# 01_FPGA.net
KiCad netlist of a schematic drawn in Altium Designer
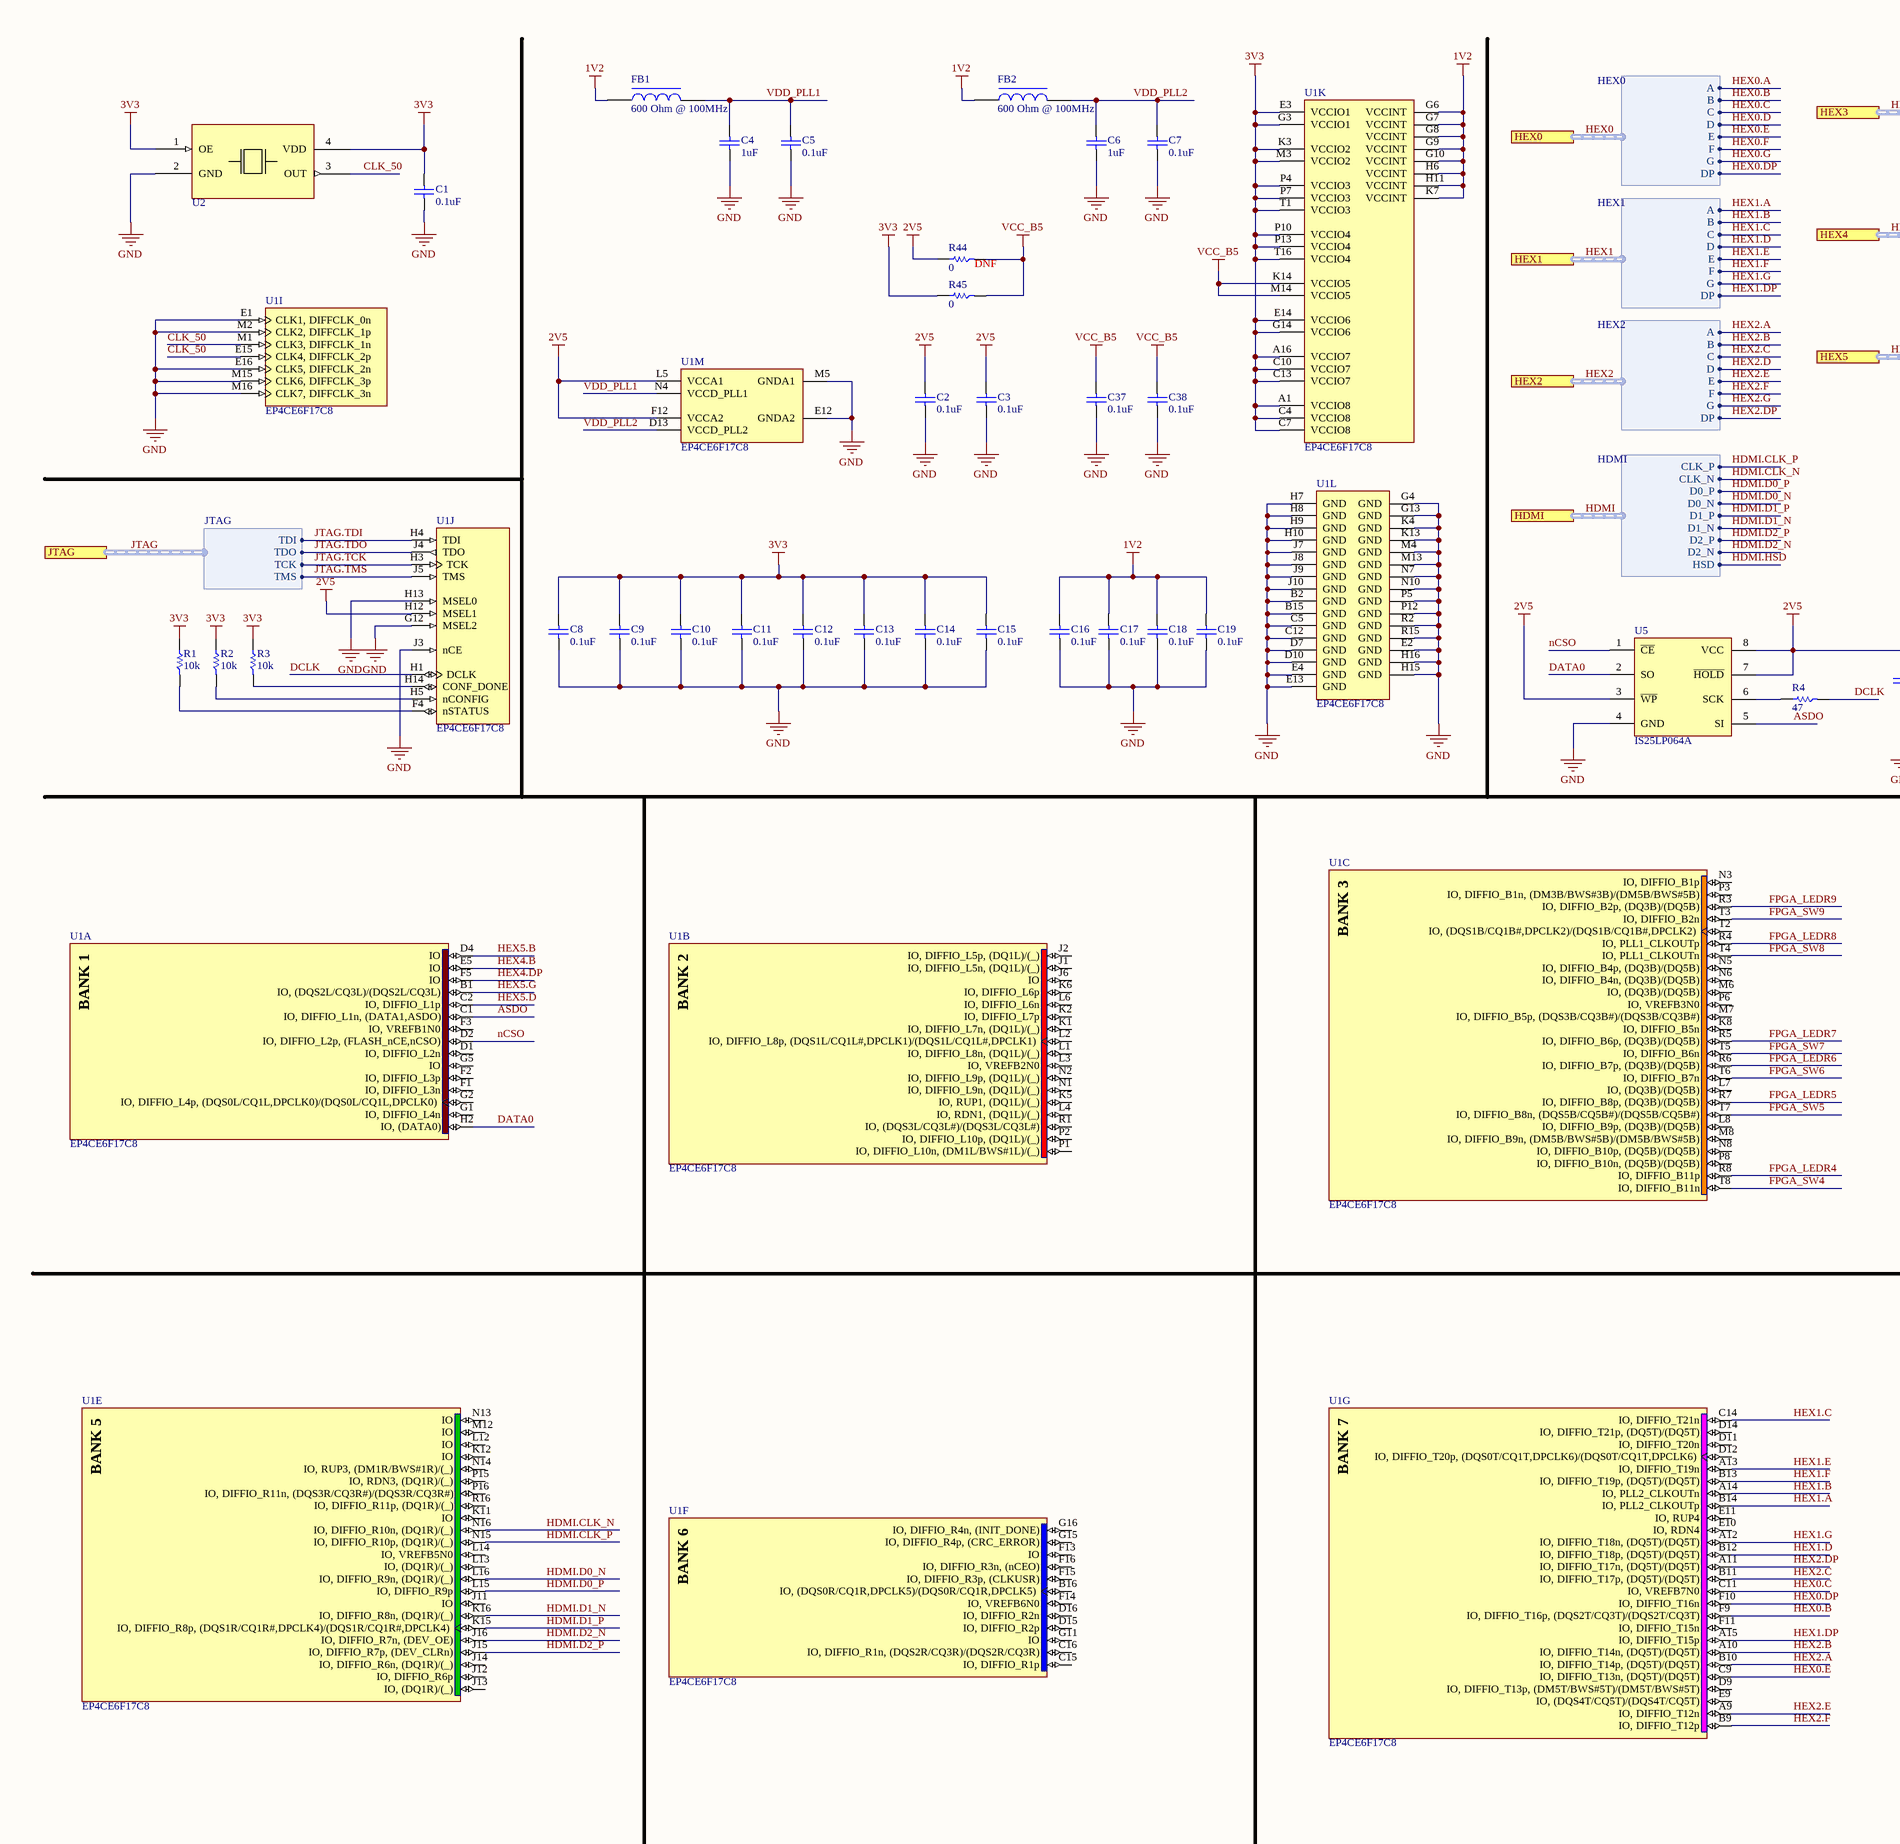
[diagram p0: 01_FPGA.SchDoc, left]
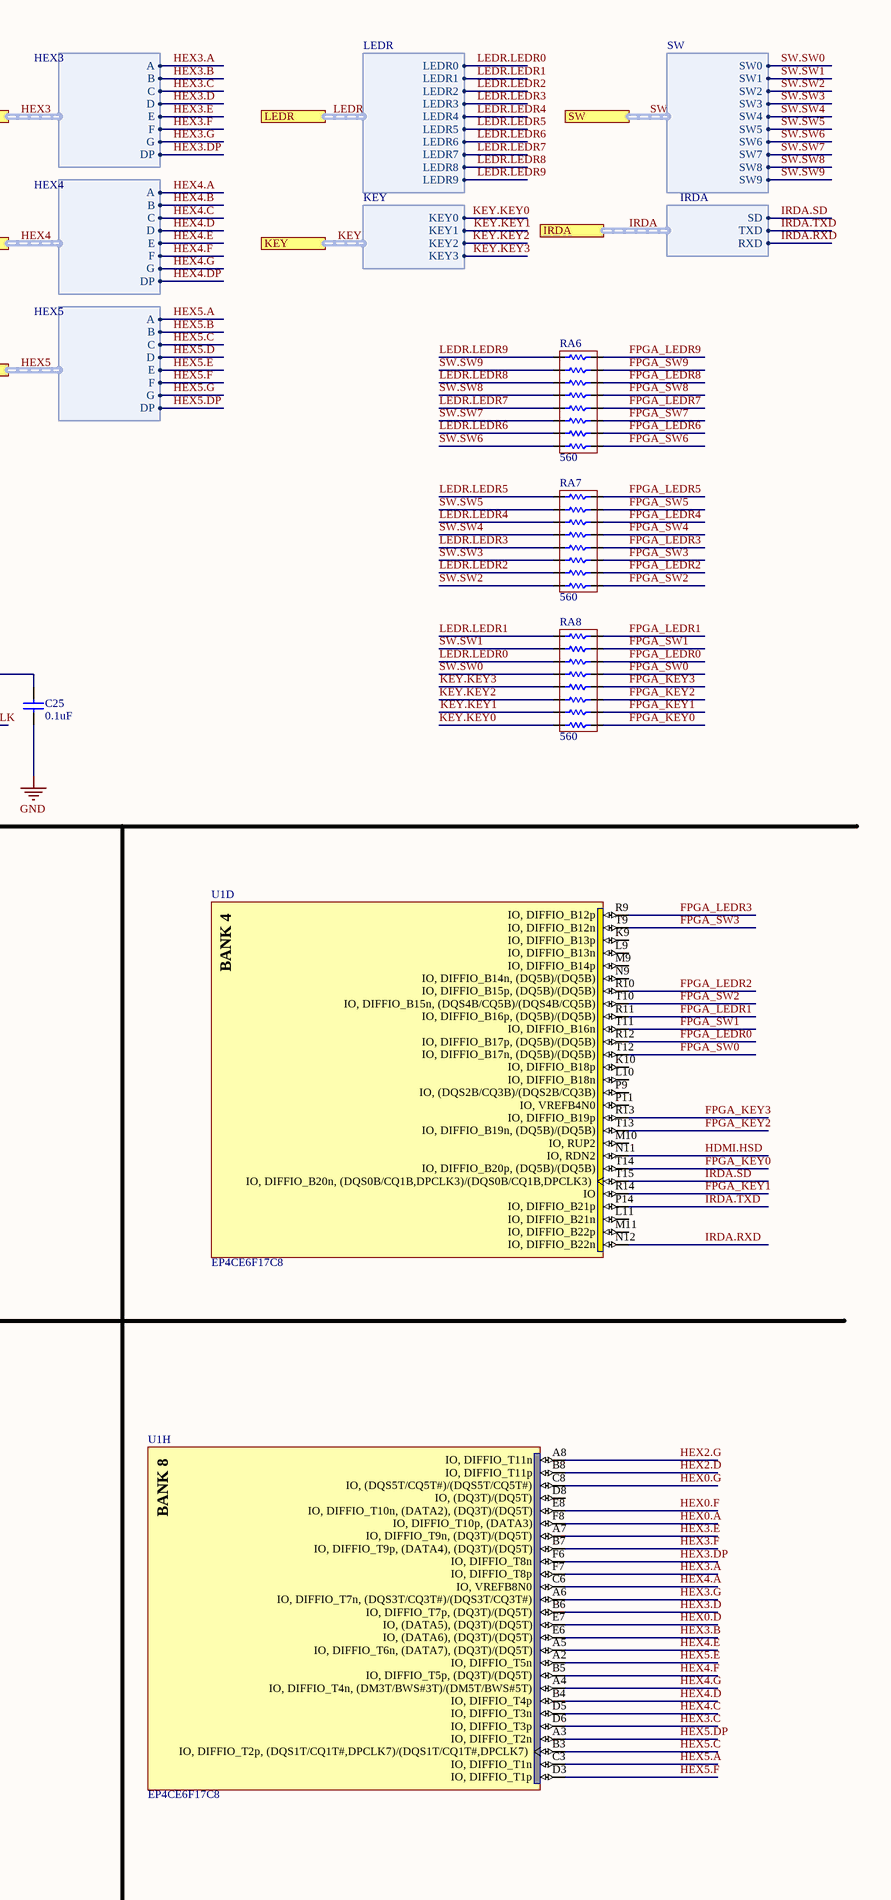
[diagram p1: 01_FPGA.SchDoc, right]

(export (version "E")
  (design (tool "Eeschema 10.0.6"))
  (components
    (comp (ref "C1")
      (value "0.1uF")
      (footprint "CAP0603R")
      (description "Capacitor")
      (libsource (lib "Quatro_SchLib") (part "C"))
    )
    (comp (ref "C2")
      (value "0.1uF")
      (footprint "CAP0603R")
      (description "Capacitor")
      (libsource (lib "Quatro_SchLib") (part "C"))
    )
    (comp (ref "C3")
      (value "0.1uF")
      (footprint "CAP0603R")
      (description "Capacitor")
      (libsource (lib "Quatro_SchLib") (part "C"))
    )
    (comp (ref "C4")
      (value "1uF")
      (footprint "CAP0603R")
      (description "Capacitor")
      (libsource (lib "Quatro_SchLib") (part "C"))
    )
    (comp (ref "C5")
      (value "0.1uF")
      (footprint "CAP0603R")
      (description "Capacitor")
      (libsource (lib "Quatro_SchLib") (part "C"))
    )
    (comp (ref "C6")
      (value "1uF")
      (footprint "CAP0603R")
      (description "Capacitor")
      (libsource (lib "Quatro_SchLib") (part "C"))
    )
    (comp (ref "C7")
      (value "0.1uF")
      (footprint "CAP0603R")
      (description "Capacitor")
      (libsource (lib "Quatro_SchLib") (part "C"))
    )
    (comp (ref "C8")
      (value "0.1uF")
      (footprint "CAP0603R")
      (description "Capacitor")
      (libsource (lib "Quatro_SchLib") (part "C"))
    )
    (comp (ref "C9")
      (value "0.1uF")
      (footprint "CAP0603R")
      (description "Capacitor")
      (libsource (lib "Quatro_SchLib") (part "C"))
    )
    (comp (ref "C10")
      (value "0.1uF")
      (footprint "CAP0603R")
      (description "Capacitor")
      (libsource (lib "Quatro_SchLib") (part "C"))
    )
    (comp (ref "C11")
      (value "0.1uF")
      (footprint "CAP0603R")
      (description "Capacitor")
      (libsource (lib "Quatro_SchLib") (part "C"))
    )
    (comp (ref "C12")
      (value "0.1uF")
      (footprint "CAP0603R")
      (description "Capacitor")
      (libsource (lib "Quatro_SchLib") (part "C"))
    )
    (comp (ref "C13")
      (value "0.1uF")
      (footprint "CAP0603R")
      (description "Capacitor")
      (libsource (lib "Quatro_SchLib") (part "C"))
    )
    (comp (ref "C14")
      (value "0.1uF")
      (footprint "CAP0603R")
      (description "Capacitor")
      (libsource (lib "Quatro_SchLib") (part "C"))
    )
    (comp (ref "C15")
      (value "0.1uF")
      (footprint "CAP0603R")
      (description "Capacitor")
      (libsource (lib "Quatro_SchLib") (part "C"))
    )
    (comp (ref "C16")
      (value "0.1uF")
      (footprint "CAP0603R")
      (description "Capacitor")
      (libsource (lib "Quatro_SchLib") (part "C"))
    )
    (comp (ref "C17")
      (value "0.1uF")
      (footprint "CAP0603R")
      (description "Capacitor")
      (libsource (lib "Quatro_SchLib") (part "C"))
    )
    (comp (ref "C18")
      (value "0.1uF")
      (footprint "CAP0603R")
      (description "Capacitor")
      (libsource (lib "Quatro_SchLib") (part "C"))
    )
    (comp (ref "C19")
      (value "0.1uF")
      (footprint "CAP0603R")
      (description "Capacitor")
      (libsource (lib "Quatro_SchLib") (part "C"))
    )
    (comp (ref "C25")
      (value "0.1uF")
      (footprint "CAP0603R")
      (description "Capacitor")
      (libsource (lib "Quatro_SchLib") (part "C"))
    )
    (comp (ref "C37")
      (value "0.1uF")
      (footprint "CAP0603R")
      (description "Capacitor")
      (libsource (lib "Quatro_SchLib") (part "C"))
    )
    (comp (ref "C38")
      (value "0.1uF")
      (footprint "CAP0603R")
      (description "Capacitor")
      (libsource (lib "Quatro_SchLib") (part "C"))
    )
    (comp (ref "FB1")
      (value "600 Ohm @ 100MHz")
      (footprint "RES0805R")
      (description "Ferrite Bead")
      (libsource (lib "Quatro_SchLib") (part "Ferrite_Bead"))
    )
    (comp (ref "FB2")
      (value "600 Ohm @ 100MHz")
      (footprint "RES0805R")
      (description "Ferrite Bead")
      (libsource (lib "Quatro_SchLib") (part "Ferrite_Bead"))
    )
    (comp (ref "R1")
      (value "10k")
      (footprint "RES0603R")
      (description "Resistor")
      (libsource (lib "Quatro_SchLib") (part "R"))
    )
    (comp (ref "R2")
      (value "10k")
      (footprint "RES0603R")
      (description "Resistor")
      (libsource (lib "Quatro_SchLib") (part "R"))
    )
    (comp (ref "R3")
      (value "10k")
      (footprint "RES0603R")
      (description "Resistor")
      (libsource (lib "Quatro_SchLib") (part "R"))
    )
    (comp (ref "R4")
      (value "47")
      (footprint "RES0603R")
      (description "Resistor")
      (libsource (lib "Quatro_SchLib") (part "R"))
    )
    (comp (ref "R44")
      (value "0")
      (footprint "RES0402R")
      (description "Resistor")
      (fields (field (name "LOAD") "DNF"))
      (libsource (lib "Quatro_SchLib") (part "R"))
    )
    (comp (ref "R45")
      (value "0")
      (footprint "RES0402R")
      (description "Resistor")
      (libsource (lib "Quatro_SchLib") (part "R"))
    )
    (comp (ref "RA6")
      (value "560")
      (footprint "EXB-2HV")
      (description "Resistor Array with 8 Isolated Resistors")
      (fields
        (field (name "Comment") "Resistor Array")
        (field (name "01 CREATED BY") "Thomas Harper (12/03/2017)")
        (field (name "PUBLISHER") "MUEEC")
      )
      (libsource (lib "Quatro_SchLib") (part "Res Array"))
    )
    (comp (ref "RA7")
      (value "560")
      (footprint "EXB-2HV")
      (description "Resistor Array with 8 Isolated Resistors")
      (fields
        (field (name "Comment") "Resistor Array")
        (field (name "01 CREATED BY") "Thomas Harper (12/03/2017)")
        (field (name "PUBLISHER") "MUEEC")
      )
      (libsource (lib "Quatro_SchLib") (part "Res Array"))
    )
    (comp (ref "RA8")
      (value "560")
      (footprint "EXB-2HV")
      (description "Resistor Array with 8 Isolated Resistors")
      (fields
        (field (name "Comment") "Resistor Array")
        (field (name "01 CREATED BY") "Thomas Harper (12/03/2017)")
        (field (name "PUBLISHER") "MUEEC")
      )
      (libsource (lib "Quatro_SchLib") (part "Res Array"))
    )
    (comp (ref "U1")
      (value "EP4CE6F17C8")
      (footprint "FBGA256")
      (fields (field (name "PUBLISHER") "Altium Limited"))
      (libsource (lib "Quatro_SchLib") (part "EP4CE6F17C8"))
    )
    (comp (ref "U2")
      (value "Oscillator")
      (footprint "CRYSTAL_7x5")
      (description "OSC 50MHZ 3.3V SMD")
      (libsource (lib "Quatro_SchLib") (part "CLK_50M"))
    )
    (comp (ref "U5")
      (value "IS25LP064A")
      (footprint "SOIC-8")
      (description "64Mb Serial Flash Memory")
      (libsource (lib "Quatro_SchLib") (part "IS25LP064A"))
    )
  )
  (nets
    (net (code "13") (name "/ASDO") (class "Default")
      (node (ref "U1") (pin "C1") (pinfunction "IO,_DIFFIO_L1n,_(DATA1,ASDO)_C1") (pintype "bidirectional"))
      (node (ref "U5") (pin "5") (pinfunction "SI_5") (pintype "passive"))
    )
    (net (code "14") (name "/CLK_50") (class "Default")
      (node (ref "U1") (pin "E15") (pinfunction "CLK4,_DIFFCLK_2p_E15") (pintype "input"))
      (node (ref "U1") (pin "M1") (pinfunction "CLK3,_DIFFCLK_1n_M1") (pintype "input"))
      (node (ref "U2") (pin "3") (pinfunction "OUT_3") (pintype "output"))
    )
    (net (code "15") (name "/DATA0") (class "Default")
      (node (ref "U1") (pin "H2") (pinfunction "IO,_(DATA0)_H2") (pintype "bidirectional"))
      (node (ref "U5") (pin "2") (pinfunction "SO_2") (pintype "passive"))
    )
    (net (code "16") (name "/DCLK") (class "Default")
      (node (ref "R4") (pin "1") (pintype "passive"))
      (node (ref "U1") (pin "H1") (pinfunction "DCLK_H1") (pintype "bidirectional"))
    )
    (net (code "17") (name "/FPGA_KEY0") (class "Default")
      (node (ref "RA8") (pin "9") (pintype "passive"))
      (node (ref "U1") (pin "T14") (pinfunction "IO,_DIFFIO_B20p,_(DQ5B)/(DQ5B)_T14") (pintype "bidirectional"))
    )
    (net (code "18") (name "/FPGA_KEY1") (class "Default")
      (node (ref "RA8") (pin "10") (pintype "passive"))
      (node (ref "U1") (pin "R14") (pinfunction "IO_R14") (pintype "bidirectional"))
    )
    (net (code "19") (name "/FPGA_KEY2") (class "Default")
      (node (ref "RA8") (pin "11") (pintype "passive"))
      (node (ref "U1") (pin "T13") (pinfunction "IO,_DIFFIO_B19n,_(DQ5B)/(DQ5B)_T13") (pintype "bidirectional"))
    )
    (net (code "20") (name "/FPGA_KEY3") (class "Default")
      (node (ref "RA8") (pin "12") (pintype "passive"))
      (node (ref "U1") (pin "R13") (pinfunction "IO,_DIFFIO_B19p_R13") (pintype "bidirectional"))
    )
    (net (code "21") (name "/FPGA_LEDR0") (class "Default")
      (node (ref "RA8") (pin "14") (pintype "passive"))
      (node (ref "U1") (pin "R12") (pinfunction "IO,_DIFFIO_B17p,_(DQ5B)/(DQ5B)_R12") (pintype "bidirectional"))
    )
    (net (code "22") (name "/FPGA_LEDR1") (class "Default")
      (node (ref "RA8") (pin "16") (pintype "passive"))
      (node (ref "U1") (pin "R11") (pinfunction "IO,_DIFFIO_B16p,_(DQ5B)/(DQ5B)_R11") (pintype "bidirectional"))
    )
    (net (code "23") (name "/FPGA_LEDR2") (class "Default")
      (node (ref "RA7") (pin "10") (pintype "passive"))
      (node (ref "U1") (pin "R10") (pinfunction "IO,_DIFFIO_B15p,_(DQ5B)/(DQ5B)_R10") (pintype "bidirectional"))
    )
    (net (code "24") (name "/FPGA_LEDR3") (class "Default")
      (node (ref "RA7") (pin "12") (pintype "passive"))
      (node (ref "U1") (pin "R9") (pinfunction "IO,_DIFFIO_B12p_R9") (pintype "bidirectional"))
    )
    (net (code "25") (name "/FPGA_LEDR4") (class "Default")
      (node (ref "RA7") (pin "14") (pintype "passive"))
      (node (ref "U1") (pin "R8") (pinfunction "IO,_DIFFIO_B11p_R8") (pintype "bidirectional"))
    )
    (net (code "26") (name "/FPGA_LEDR5") (class "Default")
      (node (ref "RA7") (pin "16") (pintype "passive"))
      (node (ref "U1") (pin "R7") (pinfunction "IO,_DIFFIO_B8p,_(DQ3B)/(DQ5B)_R7") (pintype "bidirectional"))
    )
    (net (code "27") (name "/FPGA_LEDR6") (class "Default")
      (node (ref "RA6") (pin "10") (pintype "passive"))
      (node (ref "U1") (pin "R6") (pinfunction "IO,_DIFFIO_B7p,_(DQ3B)/(DQ5B)_R6") (pintype "bidirectional"))
    )
    (net (code "28") (name "/FPGA_LEDR7") (class "Default")
      (node (ref "RA6") (pin "12") (pintype "passive"))
      (node (ref "U1") (pin "R5") (pinfunction "IO,_DIFFIO_B6p,_(DQ3B)/(DQ5B)_R5") (pintype "bidirectional"))
    )
    (net (code "29") (name "/FPGA_LEDR8") (class "Default")
      (node (ref "RA6") (pin "14") (pintype "passive"))
      (node (ref "U1") (pin "R4") (pinfunction "IO,_PLL1_CLKOUTp_R4") (pintype "bidirectional"))
    )
    (net (code "30") (name "/FPGA_LEDR9") (class "Default")
      (node (ref "RA6") (pin "16") (pintype "passive"))
      (node (ref "U1") (pin "R3") (pinfunction "IO,_DIFFIO_B2p,_(DQ3B)/(DQ5B)_R3") (pintype "bidirectional"))
    )
    (net (code "31") (name "/FPGA_SW0") (class "Default")
      (node (ref "RA8") (pin "13") (pintype "passive"))
      (node (ref "U1") (pin "T12") (pinfunction "IO,_DIFFIO_B17n,_(DQ5B)/(DQ5B)_T12") (pintype "bidirectional"))
    )
    (net (code "32") (name "/FPGA_SW1") (class "Default")
      (node (ref "RA8") (pin "15") (pintype "passive"))
      (node (ref "U1") (pin "T11") (pinfunction "IO,_DIFFIO_B16n_T11") (pintype "bidirectional"))
    )
    (net (code "33") (name "/FPGA_SW2") (class "Default")
      (node (ref "RA7") (pin "9") (pintype "passive"))
      (node (ref "U1") (pin "T10") (pinfunction "IO,_DIFFIO_B15n,_(DQS4B/CQ5B)/(DQS4B/CQ5B)_T10") (pintype "bidirectional"))
    )
    (net (code "34") (name "/FPGA_SW3") (class "Default")
      (node (ref "RA7") (pin "11") (pintype "passive"))
      (node (ref "U1") (pin "T9") (pinfunction "IO,_DIFFIO_B12n_T9") (pintype "bidirectional"))
    )
    (net (code "35") (name "/FPGA_SW4") (class "Default")
      (node (ref "RA7") (pin "13") (pintype "passive"))
      (node (ref "U1") (pin "T8") (pinfunction "IO,_DIFFIO_B11n_T8") (pintype "bidirectional"))
    )
    (net (code "36") (name "/FPGA_SW5") (class "Default")
      (node (ref "RA7") (pin "15") (pintype "passive"))
      (node (ref "U1") (pin "T7") (pinfunction "IO,_DIFFIO_B8n,_(DQS5B/CQ5B#)/(DQS5B/CQ5B#)_T7") (pintype "bidirectional"))
    )
    (net (code "37") (name "/FPGA_SW6") (class "Default")
      (node (ref "RA6") (pin "9") (pintype "passive"))
      (node (ref "U1") (pin "T6") (pinfunction "IO,_DIFFIO_B7n_T6") (pintype "bidirectional"))
    )
    (net (code "38") (name "/FPGA_SW7") (class "Default")
      (node (ref "RA6") (pin "11") (pintype "passive"))
      (node (ref "U1") (pin "T5") (pinfunction "IO,_DIFFIO_B6n_T5") (pintype "bidirectional"))
    )
    (net (code "39") (name "/FPGA_SW8") (class "Default")
      (node (ref "RA6") (pin "13") (pintype "passive"))
      (node (ref "U1") (pin "T4") (pinfunction "IO,_PLL1_CLKOUTn_T4") (pintype "bidirectional"))
    )
    (net (code "40") (name "/FPGA_SW9") (class "Default")
      (node (ref "RA6") (pin "15") (pintype "passive"))
      (node (ref "U1") (pin "T3") (pinfunction "IO,_DIFFIO_B2n_T3") (pintype "bidirectional"))
    )
    (net (code "41") (name "/HDMI.CLK_N") (class "Default")
      (node (ref "U1") (pin "N16") (pinfunction "IO,_DIFFIO_R10n,_(DQ1R)/(_)_N16") (pintype "bidirectional"))
    )
    (net (code "42") (name "/HDMI.CLK_P") (class "Default")
      (node (ref "U1") (pin "N15") (pinfunction "IO,_DIFFIO_R10p,_(DQ1R)/(_)_N15") (pintype "bidirectional"))
    )
    (net (code "43") (name "/HDMI.D0_N") (class "Default")
      (node (ref "U1") (pin "L16") (pinfunction "IO,_DIFFIO_R9n,_(DQ1R)/(_)_L16") (pintype "bidirectional"))
    )
    (net (code "44") (name "/HDMI.D0_P") (class "Default")
      (node (ref "U1") (pin "L15") (pinfunction "IO,_DIFFIO_R9p_L15") (pintype "bidirectional"))
    )
    (net (code "45") (name "/HDMI.D1_N") (class "Default")
      (node (ref "U1") (pin "K16") (pinfunction "IO,_DIFFIO_R8n,_(DQ1R)/(_)_K16") (pintype "bidirectional"))
    )
    (net (code "46") (name "/HDMI.D1_P") (class "Default")
      (node (ref "U1") (pin "K15") (pinfunction "IO,_DIFFIO_R8p,_(DQS1R/CQ1R#,DPCLK4)/(DQS1R/CQ1R#,DPCLK4)_K15") (pintype "bidirectional"))
    )
    (net (code "47") (name "/HDMI.D2_N") (class "Default")
      (node (ref "U1") (pin "J16") (pinfunction "IO,_DIFFIO_R7n,_(DEV_OE)_J16") (pintype "bidirectional"))
    )
    (net (code "48") (name "/HDMI.D2_P") (class "Default")
      (node (ref "U1") (pin "J15") (pinfunction "IO,_DIFFIO_R7p,_(DEV_CLRn)_J15") (pintype "bidirectional"))
    )
    (net (code "49") (name "/HDMI.HSD") (class "Default")
      (node (ref "U1") (pin "N11") (pinfunction "IO,_RDN2_N11") (pintype "bidirectional"))
    )
    (net (code "51") (name "/HEX0.A") (class "Default")
      (node (ref "U1") (pin "F8") (pinfunction "IO,_DIFFIO_T10p,_(DATA3)_F8") (pintype "bidirectional"))
    )
    (net (code "52") (name "/HEX0.B") (class "Default")
      (node (ref "U1") (pin "F9") (pinfunction "IO,_DIFFIO_T16p,_(DQS2T/CQ3T)/(DQS2T/CQ3T)_F9") (pintype "bidirectional"))
    )
    (net (code "53") (name "/HEX0.C") (class "Default")
      (node (ref "U1") (pin "C11") (pinfunction "IO,_VREFB7N0_C11") (pintype "bidirectional"))
    )
    (net (code "54") (name "/HEX0.D") (class "Default")
      (node (ref "U1") (pin "E7") (pinfunction "IO,_(DATA5),_(DQ3T)/(DQ5T)_E7") (pintype "bidirectional"))
    )
    (net (code "55") (name "/HEX0.DP") (class "Default")
      (node (ref "U1") (pin "F10") (pinfunction "IO,_DIFFIO_T16n_F10") (pintype "bidirectional"))
    )
    (net (code "56") (name "/HEX0.E") (class "Default")
      (node (ref "U1") (pin "C9") (pinfunction "IO,_DIFFIO_T13n,_(DQ5T)/(DQ5T)_C9") (pintype "bidirectional"))
    )
    (net (code "57") (name "/HEX0.F") (class "Default")
      (node (ref "U1") (pin "E8") (pinfunction "IO,_DIFFIO_T10n,_(DATA2),_(DQ3T)/(DQ5T)_E8") (pintype "bidirectional"))
    )
    (net (code "58") (name "/HEX0.G") (class "Default")
      (node (ref "U1") (pin "C8") (pinfunction "IO,_(DQS5T/CQ5T#)/(DQS5T/CQ5T#)_C8") (pintype "bidirectional"))
    )
    (net (code "60") (name "/HEX1.A") (class "Default")
      (node (ref "U1") (pin "B14") (pinfunction "IO,_PLL2_CLKOUTp_B14") (pintype "bidirectional"))
    )
    (net (code "61") (name "/HEX1.B") (class "Default")
      (node (ref "U1") (pin "A14") (pinfunction "IO,_PLL2_CLKOUTn_A14") (pintype "bidirectional"))
    )
    (net (code "62") (name "/HEX1.C") (class "Default")
      (node (ref "U1") (pin "C14") (pinfunction "IO,_DIFFIO_T21n_C14") (pintype "bidirectional"))
    )
    (net (code "63") (name "/HEX1.D") (class "Default")
      (node (ref "U1") (pin "B12") (pinfunction "IO,_DIFFIO_T18p,_(DQ5T)/(DQ5T)_B12") (pintype "bidirectional"))
    )
    (net (code "64") (name "/HEX1.DP") (class "Default")
      (node (ref "U1") (pin "A15") (pinfunction "IO,_DIFFIO_T15p_A15") (pintype "bidirectional"))
    )
    (net (code "65") (name "/HEX1.E") (class "Default")
      (node (ref "U1") (pin "A13") (pinfunction "IO,_DIFFIO_T19n_A13") (pintype "bidirectional"))
    )
    (net (code "66") (name "/HEX1.F") (class "Default")
      (node (ref "U1") (pin "B13") (pinfunction "IO,_DIFFIO_T19p,_(DQ5T)/(DQ5T)_B13") (pintype "bidirectional"))
    )
    (net (code "67") (name "/HEX1.G") (class "Default")
      (node (ref "U1") (pin "A12") (pinfunction "IO,_DIFFIO_T18n,_(DQ5T)/(DQ5T)_A12") (pintype "bidirectional"))
    )
    (net (code "69") (name "/HEX2.A") (class "Default")
      (node (ref "U1") (pin "B10") (pinfunction "IO,_DIFFIO_T14p,_(DQ5T)/(DQ5T)_B10") (pintype "bidirectional"))
    )
    (net (code "70") (name "/HEX2.B") (class "Default")
      (node (ref "U1") (pin "A10") (pinfunction "IO,_DIFFIO_T14n,_(DQ5T)/(DQ5T)_A10") (pintype "bidirectional"))
    )
    (net (code "71") (name "/HEX2.C") (class "Default")
      (node (ref "U1") (pin "B11") (pinfunction "IO,_DIFFIO_T17p,_(DQ5T)/(DQ5T)_B11") (pintype "bidirectional"))
    )
    (net (code "72") (name "/HEX2.D") (class "Default")
      (node (ref "U1") (pin "B8") (pinfunction "IO,_DIFFIO_T11p_B8") (pintype "bidirectional"))
    )
    (net (code "73") (name "/HEX2.DP") (class "Default")
      (node (ref "U1") (pin "A11") (pinfunction "IO,_DIFFIO_T17n,_(DQ5T)/(DQ5T)_A11") (pintype "bidirectional"))
    )
    (net (code "74") (name "/HEX2.E") (class "Default")
      (node (ref "U1") (pin "A9") (pinfunction "IO,_DIFFIO_T12n_A9") (pintype "bidirectional"))
    )
    (net (code "75") (name "/HEX2.F") (class "Default")
      (node (ref "U1") (pin "B9") (pinfunction "IO,_DIFFIO_T12p_B9") (pintype "bidirectional"))
    )
    (net (code "76") (name "/HEX2.G") (class "Default")
      (node (ref "U1") (pin "A8") (pinfunction "IO,_DIFFIO_T11n_A8") (pintype "bidirectional"))
    )
    (net (code "78") (name "/HEX3.A") (class "Default")
      (node (ref "U1") (pin "F7") (pinfunction "IO,_DIFFIO_T8p_F7") (pintype "bidirectional"))
    )
    (net (code "79") (name "/HEX3.B") (class "Default")
      (node (ref "U1") (pin "E6") (pinfunction "IO,_(DATA6),_(DQ3T)/(DQ5T)_E6") (pintype "bidirectional"))
    )
    (net (code "80") (name "/HEX3.C") (class "Default")
      (node (ref "U1") (pin "D6") (pinfunction "IO,_DIFFIO_T3p_D6") (pintype "bidirectional"))
    )
    (net (code "81") (name "/HEX3.D") (class "Default")
      (node (ref "U1") (pin "B6") (pinfunction "IO,_DIFFIO_T7p,_(DQ3T)/(DQ5T)_B6") (pintype "bidirectional"))
    )
    (net (code "82") (name "/HEX3.DP") (class "Default")
      (node (ref "U1") (pin "F6") (pinfunction "IO,_DIFFIO_T8n_F6") (pintype "bidirectional"))
    )
    (net (code "83") (name "/HEX3.E") (class "Default")
      (node (ref "U1") (pin "A7") (pinfunction "IO,_DIFFIO_T9n,_(DQ3T)/(DQ5T)_A7") (pintype "bidirectional"))
    )
    (net (code "84") (name "/HEX3.F") (class "Default")
      (node (ref "U1") (pin "B7") (pinfunction "IO,_DIFFIO_T9p,_(DATA4),_(DQ3T)/(DQ5T)_B7") (pintype "bidirectional"))
    )
    (net (code "85") (name "/HEX3.G") (class "Default")
      (node (ref "U1") (pin "A6") (pinfunction "IO,_DIFFIO_T7n,_(DQS3T/CQ3T#)/(DQS3T/CQ3T#)_A6") (pintype "bidirectional"))
    )
    (net (code "87") (name "/HEX4.A") (class "Default")
      (node (ref "U1") (pin "C6") (pinfunction "IO,_VREFB8N0_C6") (pintype "bidirectional"))
    )
    (net (code "88") (name "/HEX4.B") (class "Default")
      (node (ref "U1") (pin "E5") (pinfunction "IO_E5") (pintype "bidirectional"))
    )
    (net (code "89") (name "/HEX4.C") (class "Default")
      (node (ref "U1") (pin "D5") (pinfunction "IO,_DIFFIO_T3n_D5") (pintype "bidirectional"))
    )
    (net (code "90") (name "/HEX4.D") (class "Default")
      (node (ref "U1") (pin "B4") (pinfunction "IO,_DIFFIO_T4p_B4") (pintype "bidirectional"))
    )
    (net (code "91") (name "/HEX4.DP") (class "Default")
      (node (ref "U1") (pin "F5") (pinfunction "IO_F5") (pintype "bidirectional"))
    )
    (net (code "92") (name "/HEX4.E") (class "Default")
      (node (ref "U1") (pin "A5") (pinfunction "IO,_DIFFIO_T6n,_(DATA7),_(DQ3T)/(DQ5T)_A5") (pintype "bidirectional"))
    )
    (net (code "93") (name "/HEX4.F") (class "Default")
      (node (ref "U1") (pin "B5") (pinfunction "IO,_DIFFIO_T5p,_(DQ3T)/(DQ5T)_B5") (pintype "bidirectional"))
    )
    (net (code "94") (name "/HEX4.G") (class "Default")
      (node (ref "U1") (pin "A4") (pinfunction "IO,_DIFFIO_T4n,_(DM3T/BWS#3T)/(DM5T/BWS#5T)_A4") (pintype "bidirectional"))
    )
    (net (code "96") (name "/HEX5.A") (class "Default")
      (node (ref "U1") (pin "C3") (pinfunction "IO,_DIFFIO_T1n_C3") (pintype "bidirectional"))
    )
    (net (code "97") (name "/HEX5.B") (class "Default")
      (node (ref "U1") (pin "D4") (pinfunction "IO_D4") (pintype "bidirectional"))
    )
    (net (code "98") (name "/HEX5.C") (class "Default")
      (node (ref "U1") (pin "B3") (pinfunction "IO,_DIFFIO_T2p,_(DQS1T/CQ1T#,DPCLK7)/(DQS1T/CQ1T#,DPCLK7)_B3") (pintype "bidirectional"))
    )
    (net (code "99") (name "/HEX5.D") (class "Default")
      (node (ref "U1") (pin "C2") (pinfunction "IO,_DIFFIO_L1p_C2") (pintype "bidirectional"))
    )
    (net (code "100") (name "/HEX5.DP") (class "Default")
      (node (ref "U1") (pin "A3") (pinfunction "IO,_DIFFIO_T2n_A3") (pintype "bidirectional"))
    )
    (net (code "101") (name "/HEX5.E") (class "Default")
      (node (ref "U1") (pin "A2") (pinfunction "IO,_DIFFIO_T5n_A2") (pintype "bidirectional"))
    )
    (net (code "102") (name "/HEX5.F") (class "Default")
      (node (ref "U1") (pin "D3") (pinfunction "IO,_DIFFIO_T1p_D3") (pintype "bidirectional"))
    )
    (net (code "103") (name "/HEX5.G") (class "Default")
      (node (ref "U1") (pin "B1") (pinfunction "IO,_(DQS2L/CQ3L)/(DQS2L/CQ3L)_B1") (pintype "bidirectional"))
    )
    (net (code "105") (name "/IRDA.RXD") (class "Default")
      (node (ref "U1") (pin "N12") (pinfunction "IO,_DIFFIO_B22n_N12") (pintype "bidirectional"))
    )
    (net (code "106") (name "/IRDA.SD") (class "Default")
      (node (ref "U1") (pin "T15") (pinfunction "IO,_DIFFIO_B20n,_(DQS0B/CQ1B,DPCLK3)/(DQS0B/CQ1B,DPCLK3)_T15") (pintype "bidirectional"))
    )
    (net (code "107") (name "/IRDA.TXD") (class "Default")
      (node (ref "U1") (pin "P14") (pinfunction "IO,_DIFFIO_B21p_P14") (pintype "bidirectional"))
    )
    (net (code "109") (name "/JTAG.TCK") (class "Default")
      (node (ref "U1") (pin "H3") (pinfunction "TCK_H3") (pintype "input"))
    )
    (net (code "110") (name "/JTAG.TDI") (class "Default")
      (node (ref "U1") (pin "H4") (pinfunction "TDI_H4") (pintype "input"))
    )
    (net (code "111") (name "/JTAG.TDO") (class "Default")
      (node (ref "U1") (pin "J4") (pinfunction "TDO_J4") (pintype "output"))
    )
    (net (code "112") (name "/JTAG.TMS") (class "Default")
      (node (ref "U1") (pin "J5") (pinfunction "TMS_J5") (pintype "input"))
    )
    (net (code "114") (name "/KEY.KEY0") (class "Default") (node (ref "RA8") (pin "8") (pintype "passive")))
    (net (code "115") (name "/KEY.KEY1") (class "Default") (node (ref "RA8") (pin "7") (pintype "passive")))
    (net (code "116") (name "/KEY.KEY2") (class "Default") (node (ref "RA8") (pin "6") (pintype "passive")))
    (net (code "117") (name "/KEY.KEY3") (class "Default") (node (ref "RA8") (pin "5") (pintype "passive")))
    (net (code "119") (name "/LEDR.LEDR0") (class "Default") (node (ref "RA8") (pin "3") (pintype "passive")))
    (net (code "120") (name "/LEDR.LEDR1") (class "Default") (node (ref "RA8") (pin "1") (pintype "passive")))
    (net (code "121") (name "/LEDR.LEDR2") (class "Default") (node (ref "RA7") (pin "7") (pintype "passive")))
    (net (code "122") (name "/LEDR.LEDR3") (class "Default") (node (ref "RA7") (pin "5") (pintype "passive")))
    (net (code "123") (name "/LEDR.LEDR4") (class "Default") (node (ref "RA7") (pin "3") (pintype "passive")))
    (net (code "124") (name "/LEDR.LEDR5") (class "Default") (node (ref "RA7") (pin "1") (pintype "passive")))
    (net (code "125") (name "/LEDR.LEDR6") (class "Default") (node (ref "RA6") (pin "7") (pintype "passive")))
    (net (code "126") (name "/LEDR.LEDR7") (class "Default") (node (ref "RA6") (pin "5") (pintype "passive")))
    (net (code "127") (name "/LEDR.LEDR8") (class "Default") (node (ref "RA6") (pin "3") (pintype "passive")))
    (net (code "128") (name "/LEDR.LEDR9") (class "Default") (node (ref "RA6") (pin "1") (pintype "passive")))
    (net (code "130") (name "/SW.SW0") (class "Default") (node (ref "RA8") (pin "4") (pintype "passive")))
    (net (code "131") (name "/SW.SW1") (class "Default") (node (ref "RA8") (pin "2") (pintype "passive")))
    (net (code "132") (name "/SW.SW2") (class "Default") (node (ref "RA7") (pin "8") (pintype "passive")))
    (net (code "133") (name "/SW.SW3") (class "Default") (node (ref "RA7") (pin "6") (pintype "passive")))
    (net (code "134") (name "/SW.SW4") (class "Default") (node (ref "RA7") (pin "4") (pintype "passive")))
    (net (code "135") (name "/SW.SW5") (class "Default") (node (ref "RA7") (pin "2") (pintype "passive")))
    (net (code "136") (name "/SW.SW6") (class "Default") (node (ref "RA6") (pin "8") (pintype "passive")))
    (net (code "137") (name "/SW.SW7") (class "Default") (node (ref "RA6") (pin "6") (pintype "passive")))
    (net (code "138") (name "/SW.SW8") (class "Default") (node (ref "RA6") (pin "4") (pintype "passive")))
    (net (code "139") (name "/SW.SW9") (class "Default") (node (ref "RA6") (pin "2") (pintype "passive")))
    (net (code "141") (name "/VDD_PLL1") (class "Default")
      (node (ref "C4") (pin "1") (pinfunction "1_1") (pintype "passive"))
      (node (ref "C5") (pin "1") (pinfunction "1_1") (pintype "passive"))
      (node (ref "FB1") (pin "2") (pinfunction "2_2") (pintype "passive"))
      (node (ref "U1") (pin "N4") (pinfunction "VCCD_PLL1_N4") (pintype "power_in"))
    )
    (net (code "142") (name "/VDD_PLL2") (class "Default")
      (node (ref "C6") (pin "1") (pinfunction "1_1") (pintype "passive"))
      (node (ref "C7") (pin "1") (pinfunction "1_1") (pintype "passive"))
      (node (ref "FB2") (pin "2") (pinfunction "2_2") (pintype "passive"))
      (node (ref "U1") (pin "D13") (pinfunction "VCCD_PLL2_D13") (pintype "power_in"))
    )
    (net (code "143") (name "/nCSO") (class "Default")
      (node (ref "U1") (pin "D2") (pinfunction "IO,_DIFFIO_L2p,_(FLASH_nCE,nCSO)_D2") (pintype "bidirectional"))
      (node (ref "U5") (pin "1") (pinfunction "~{CE}_1") (pintype "passive"))
    )
    (net (code "144") (name "1V2") (class "Default")
      (node (ref "C16") (pin "1") (pinfunction "1_1") (pintype "passive"))
      (node (ref "C17") (pin "1") (pinfunction "1_1") (pintype "passive"))
      (node (ref "C18") (pin "1") (pinfunction "1_1") (pintype "passive"))
      (node (ref "C19") (pin "1") (pinfunction "1_1") (pintype "passive"))
      (node (ref "FB1") (pin "1") (pinfunction "1_1") (pintype "passive"))
      (node (ref "FB2") (pin "1") (pinfunction "1_1") (pintype "passive"))
      (node (ref "U1") (pin "G10") (pinfunction "VCCINT_G10") (pintype "power_in"))
      (node (ref "U1") (pin "G6") (pinfunction "VCCINT_G6") (pintype "power_in"))
      (node (ref "U1") (pin "G7") (pinfunction "VCCINT_G7") (pintype "power_in"))
      (node (ref "U1") (pin "G8") (pinfunction "VCCINT_G8") (pintype "power_in"))
      (node (ref "U1") (pin "G9") (pinfunction "VCCINT_G9") (pintype "power_in"))
      (node (ref "U1") (pin "H11") (pinfunction "VCCINT_H11") (pintype "power_in"))
      (node (ref "U1") (pin "H6") (pinfunction "VCCINT_H6") (pintype "power_in"))
      (node (ref "U1") (pin "K7") (pinfunction "VCCINT_K7") (pintype "power_in"))
    )
    (net (code "145") (name "2V5") (class "Default")
      (node (ref "C2") (pin "1") (pinfunction "1_1") (pintype "passive"))
      (node (ref "C25") (pin "1") (pinfunction "1_1") (pintype "passive"))
      (node (ref "C3") (pin "1") (pinfunction "1_1") (pintype "passive"))
      (node (ref "R44") (pin "2") (pintype "passive"))
      (node (ref "U1") (pin "F12") (pinfunction "VCCA2_F12") (pintype "power_in"))
      (node (ref "U1") (pin "H12") (pinfunction "MSEL1_H12") (pintype "input"))
      (node (ref "U1") (pin "L5") (pinfunction "VCCA1_L5") (pintype "power_in"))
      (node (ref "U5") (pin "3") (pinfunction "~{WP}_3") (pintype "passive"))
      (node (ref "U5") (pin "7") (pinfunction "~{HOLD}_7") (pintype "passive"))
      (node (ref "U5") (pin "8") (pinfunction "VCC_8") (pintype "passive"))
    )
    (net (code "146") (name "3V3") (class "Default")
      (node (ref "C1") (pin "1") (pinfunction "1_1") (pintype "passive"))
      (node (ref "C10") (pin "1") (pinfunction "1_1") (pintype "passive"))
      (node (ref "C11") (pin "1") (pinfunction "1_1") (pintype "passive"))
      (node (ref "C12") (pin "1") (pinfunction "1_1") (pintype "passive"))
      (node (ref "C13") (pin "1") (pinfunction "1_1") (pintype "passive"))
      (node (ref "C14") (pin "1") (pinfunction "1_1") (pintype "passive"))
      (node (ref "C15") (pin "1") (pinfunction "1_1") (pintype "passive"))
      (node (ref "C8") (pin "1") (pinfunction "1_1") (pintype "passive"))
      (node (ref "C9") (pin "1") (pinfunction "1_1") (pintype "passive"))
      (node (ref "R1") (pin "2") (pintype "passive"))
      (node (ref "R2") (pin "2") (pintype "passive"))
      (node (ref "R3") (pin "2") (pintype "passive"))
      (node (ref "R45") (pin "2") (pintype "passive"))
      (node (ref "U1") (pin "A1") (pinfunction "VCCIO8_A1") (pintype "power_in"))
      (node (ref "U1") (pin "A16") (pinfunction "VCCIO7_A16") (pintype "power_in"))
      (node (ref "U1") (pin "C10") (pinfunction "VCCIO7_C10") (pintype "power_in"))
      (node (ref "U1") (pin "C13") (pinfunction "VCCIO7_C13") (pintype "power_in"))
      (node (ref "U1") (pin "C4") (pinfunction "VCCIO8_C4") (pintype "power_in"))
      (node (ref "U1") (pin "C7") (pinfunction "VCCIO8_C7") (pintype "power_in"))
      (node (ref "U1") (pin "E14") (pinfunction "VCCIO6_E14") (pintype "power_in"))
      (node (ref "U1") (pin "E3") (pinfunction "VCCIO1_E3") (pintype "power_in"))
      (node (ref "U1") (pin "G14") (pinfunction "VCCIO6_G14") (pintype "power_in"))
      (node (ref "U1") (pin "G3") (pinfunction "VCCIO1_G3") (pintype "power_in"))
      (node (ref "U1") (pin "K3") (pinfunction "VCCIO2_K3") (pintype "power_in"))
      (node (ref "U1") (pin "M3") (pinfunction "VCCIO2_M3") (pintype "power_in"))
      (node (ref "U1") (pin "P10") (pinfunction "VCCIO4_P10") (pintype "power_in"))
      (node (ref "U1") (pin "P13") (pinfunction "VCCIO4_P13") (pintype "power_in"))
      (node (ref "U1") (pin "P4") (pinfunction "VCCIO3_P4") (pintype "power_in"))
      (node (ref "U1") (pin "P7") (pinfunction "VCCIO3_P7") (pintype "power_in"))
      (node (ref "U1") (pin "T1") (pinfunction "VCCIO3_T1") (pintype "power_in"))
      (node (ref "U1") (pin "T16") (pinfunction "VCCIO4_T16") (pintype "power_in"))
      (node (ref "U2") (pin "1") (pinfunction "OE_1") (pintype "input"))
      (node (ref "U2") (pin "4") (pinfunction "VDD_4") (pintype "power_in"))
    )
    (net (code "147") (name "GND") (class "Default")
      (node (ref "C1") (pin "2") (pinfunction "2_2") (pintype "passive"))
      (node (ref "C10") (pin "2") (pinfunction "2_2") (pintype "passive"))
      (node (ref "C11") (pin "2") (pinfunction "2_2") (pintype "passive"))
      (node (ref "C12") (pin "2") (pinfunction "2_2") (pintype "passive"))
      (node (ref "C13") (pin "2") (pinfunction "2_2") (pintype "passive"))
      (node (ref "C14") (pin "2") (pinfunction "2_2") (pintype "passive"))
      (node (ref "C15") (pin "2") (pinfunction "2_2") (pintype "passive"))
      (node (ref "C16") (pin "2") (pinfunction "2_2") (pintype "passive"))
      (node (ref "C17") (pin "2") (pinfunction "2_2") (pintype "passive"))
      (node (ref "C18") (pin "2") (pinfunction "2_2") (pintype "passive"))
      (node (ref "C19") (pin "2") (pinfunction "2_2") (pintype "passive"))
      (node (ref "C2") (pin "2") (pinfunction "2_2") (pintype "passive"))
      (node (ref "C25") (pin "2") (pinfunction "2_2") (pintype "passive"))
      (node (ref "C3") (pin "2") (pinfunction "2_2") (pintype "passive"))
      (node (ref "C37") (pin "2") (pinfunction "2_2") (pintype "passive"))
      (node (ref "C38") (pin "2") (pinfunction "2_2") (pintype "passive"))
      (node (ref "C4") (pin "2") (pinfunction "2_2") (pintype "passive"))
      (node (ref "C5") (pin "2") (pinfunction "2_2") (pintype "passive"))
      (node (ref "C6") (pin "2") (pinfunction "2_2") (pintype "passive"))
      (node (ref "C7") (pin "2") (pinfunction "2_2") (pintype "passive"))
      (node (ref "C8") (pin "2") (pinfunction "2_2") (pintype "passive"))
      (node (ref "C9") (pin "2") (pinfunction "2_2") (pintype "passive"))
      (node (ref "U1") (pin "B15") (pinfunction "GND_B15") (pintype "power_in"))
      (node (ref "U1") (pin "B2") (pinfunction "GND_B2") (pintype "power_in"))
      (node (ref "U1") (pin "C12") (pinfunction "GND_C12") (pintype "power_in"))
      (node (ref "U1") (pin "C5") (pinfunction "GND_C5") (pintype "power_in"))
      (node (ref "U1") (pin "D10") (pinfunction "GND_D10") (pintype "power_in"))
      (node (ref "U1") (pin "D7") (pinfunction "GND_D7") (pintype "power_in"))
      (node (ref "U1") (pin "E1") (pinfunction "CLK1,_DIFFCLK_0n_E1") (pintype "input"))
      (node (ref "U1") (pin "E12") (pinfunction "GNDA2_E12") (pintype "power_in"))
      (node (ref "U1") (pin "E13") (pinfunction "GND_E13") (pintype "power_in"))
      (node (ref "U1") (pin "E16") (pinfunction "CLK5,_DIFFCLK_2n_E16") (pintype "input"))
      (node (ref "U1") (pin "E2") (pinfunction "GND_E2") (pintype "power_in"))
      (node (ref "U1") (pin "E4") (pinfunction "GND_E4") (pintype "power_in"))
      (node (ref "U1") (pin "G12") (pinfunction "MSEL2_G12") (pintype "input"))
      (node (ref "U1") (pin "G13") (pinfunction "GND_G13") (pintype "power_in"))
      (node (ref "U1") (pin "G4") (pinfunction "GND_G4") (pintype "power_in"))
      (node (ref "U1") (pin "H10") (pinfunction "GND_H10") (pintype "power_in"))
      (node (ref "U1") (pin "H13") (pinfunction "MSEL0_H13") (pintype "input"))
      (node (ref "U1") (pin "H15") (pinfunction "GND_H15") (pintype "power_in"))
      (node (ref "U1") (pin "H16") (pinfunction "GND_H16") (pintype "power_in"))
      (node (ref "U1") (pin "H7") (pinfunction "GND_H7") (pintype "power_in"))
      (node (ref "U1") (pin "H8") (pinfunction "GND_H8") (pintype "power_in"))
      (node (ref "U1") (pin "H9") (pinfunction "GND_H9") (pintype "power_in"))
      (node (ref "U1") (pin "J10") (pinfunction "GND_J10") (pintype "power_in"))
      (node (ref "U1") (pin "J3") (pinfunction "nCE_J3") (pintype "input"))
      (node (ref "U1") (pin "J7") (pinfunction "GND_J7") (pintype "power_in"))
      (node (ref "U1") (pin "J8") (pinfunction "GND_J8") (pintype "power_in"))
      (node (ref "U1") (pin "J9") (pinfunction "GND_J9") (pintype "power_in"))
      (node (ref "U1") (pin "K13") (pinfunction "GND_K13") (pintype "power_in"))
      (node (ref "U1") (pin "K4") (pinfunction "GND_K4") (pintype "power_in"))
      (node (ref "U1") (pin "M13") (pinfunction "GND_M13") (pintype "power_in"))
      (node (ref "U1") (pin "M15") (pinfunction "CLK6,_DIFFCLK_3p_M15") (pintype "input"))
      (node (ref "U1") (pin "M16") (pinfunction "CLK7,_DIFFCLK_3n_M16") (pintype "input"))
      (node (ref "U1") (pin "M2") (pinfunction "CLK2,_DIFFCLK_1p_M2") (pintype "input"))
      (node (ref "U1") (pin "M4") (pinfunction "GND_M4") (pintype "power_in"))
      (node (ref "U1") (pin "M5") (pinfunction "GNDA1_M5") (pintype "power_in"))
      (node (ref "U1") (pin "N10") (pinfunction "GND_N10") (pintype "power_in"))
      (node (ref "U1") (pin "N7") (pinfunction "GND_N7") (pintype "power_in"))
      (node (ref "U1") (pin "P12") (pinfunction "GND_P12") (pintype "power_in"))
      (node (ref "U1") (pin "P5") (pinfunction "GND_P5") (pintype "power_in"))
      (node (ref "U1") (pin "R15") (pinfunction "GND_R15") (pintype "power_in"))
      (node (ref "U1") (pin "R2") (pinfunction "GND_R2") (pintype "power_in"))
      (node (ref "U2") (pin "2") (pinfunction "GND_2") (pintype "power_in"))
      (node (ref "U5") (pin "4") (pinfunction "GND_4") (pintype "passive"))
    )
    (net (code "148") (name "Net-(U1J-CONF_DONE)") (class "Default")
      (node (ref "R3") (pin "1") (pintype "passive"))
      (node (ref "U1") (pin "H14") (pinfunction "CONF_DONE_H14") (pintype "bidirectional"))
    )
    (net (code "149") (name "Net-(U1J-nCONFIG)") (class "Default")
      (node (ref "R2") (pin "1") (pintype "passive"))
      (node (ref "U1") (pin "H5") (pinfunction "nCONFIG_H5") (pintype "input"))
    )
    (net (code "150") (name "Net-(U1J-nSTATUS)") (class "Default")
      (node (ref "R1") (pin "1") (pintype "passive"))
      (node (ref "U1") (pin "F4") (pinfunction "nSTATUS_F4") (pintype "bidirectional"))
    )
    (net (code "151") (name "Net-(U5-SCK)") (class "Default")
      (node (ref "R4") (pin "2") (pintype "passive"))
      (node (ref "U5") (pin "6") (pinfunction "SCK_6") (pintype "passive"))
    )
    (net (code "152") (name "VCC_B5") (class "Default")
      (node (ref "C37") (pin "1") (pinfunction "1_1") (pintype "passive"))
      (node (ref "C38") (pin "1") (pinfunction "1_1") (pintype "passive"))
      (node (ref "R44") (pin "1") (pintype "passive"))
      (node (ref "R45") (pin "1") (pintype "passive"))
      (node (ref "U1") (pin "K14") (pinfunction "VCCIO5_K14") (pintype "power_in"))
      (node (ref "U1") (pin "M14") (pinfunction "VCCIO5_M14") (pintype "power_in"))
    )
    (net (code "153") (name "unconnected-(U1A-IO,_DIFFIO_L2n-PadD1)") (class "Default")
      (node (ref "U1") (pin "D1") (pinfunction "IO,_DIFFIO_L2n_D1") (pintype "bidirectional"))
    )
    (net (code "154") (name "unconnected-(U1A-IO,_DIFFIO_L3n-PadF1)") (class "Default")
      (node (ref "U1") (pin "F1") (pinfunction "IO,_DIFFIO_L3n_F1") (pintype "bidirectional"))
    )
    (net (code "155") (name "unconnected-(U1A-IO,_DIFFIO_L3p-PadF2)") (class "Default")
      (node (ref "U1") (pin "F2") (pinfunction "IO,_DIFFIO_L3p_F2") (pintype "bidirectional"))
    )
    (net (code "156") (name "unconnected-(U1A-IO,_DIFFIO_L4n-PadG1)") (class "Default")
      (node (ref "U1") (pin "G1") (pinfunction "IO,_DIFFIO_L4n_G1") (pintype "bidirectional"))
    )
    (net (code "157") (name "unconnected-(U1A-IO,_DIFFIO_L4p,_(DQS0L{slash}CQ1L,DPCLK0){slash}(DQS0L{slash}CQ1L,DPCLK0)-PadG2)") (class "Default")
      (node (ref "U1") (pin "G2") (pinfunction "IO,_DIFFIO_L4p,_(DQS0L/CQ1L,DPCLK0)/(DQS0L/CQ1L,DPCLK0)_G2") (pintype "bidirectional"))
    )
    (net (code "158") (name "unconnected-(U1A-IO,_VREFB1N0-PadF3)") (class "Default")
      (node (ref "U1") (pin "F3") (pinfunction "IO,_VREFB1N0_F3") (pintype "bidirectional"))
    )
    (net (code "159") (name "unconnected-(U1A-IO-PadG5)") (class "Default")
      (node (ref "U1") (pin "G5") (pinfunction "IO_G5") (pintype "bidirectional"))
    )
    (net (code "160") (name "unconnected-(U1B-IO,_(DQS3L{slash}CQ3L#){slash}(DQS3L{slash}CQ3L#)-PadR1)") (class "Default")
      (node (ref "U1") (pin "R1") (pinfunction "IO,_(DQS3L/CQ3L#)/(DQS3L/CQ3L#)_R1") (pintype "bidirectional"))
    )
    (net (code "161") (name "unconnected-(U1B-IO,_DIFFIO_L5n,_(DQ1L){slash}(_)-PadJ1)") (class "Default")
      (node (ref "U1") (pin "J1") (pinfunction "IO,_DIFFIO_L5n,_(DQ1L)/(_)_J1") (pintype "bidirectional"))
    )
    (net (code "162") (name "unconnected-(U1B-IO,_DIFFIO_L5p,_(DQ1L){slash}(_)-PadJ2)") (class "Default")
      (node (ref "U1") (pin "J2") (pinfunction "IO,_DIFFIO_L5p,_(DQ1L)/(_)_J2") (pintype "bidirectional"))
    )
    (net (code "163") (name "unconnected-(U1B-IO,_DIFFIO_L6n-PadL6)") (class "Default")
      (node (ref "U1") (pin "L6") (pinfunction "IO,_DIFFIO_L6n_L6") (pintype "bidirectional"))
    )
    (net (code "164") (name "unconnected-(U1B-IO,_DIFFIO_L6p-PadK6)") (class "Default")
      (node (ref "U1") (pin "K6") (pinfunction "IO,_DIFFIO_L6p_K6") (pintype "bidirectional"))
    )
    (net (code "165") (name "unconnected-(U1B-IO,_DIFFIO_L7n,_(DQ1L){slash}(_)-PadK1)") (class "Default")
      (node (ref "U1") (pin "K1") (pinfunction "IO,_DIFFIO_L7n,_(DQ1L)/(_)_K1") (pintype "bidirectional"))
    )
    (net (code "166") (name "unconnected-(U1B-IO,_DIFFIO_L7p-PadK2)") (class "Default")
      (node (ref "U1") (pin "K2") (pinfunction "IO,_DIFFIO_L7p_K2") (pintype "bidirectional"))
    )
    (net (code "167") (name "unconnected-(U1B-IO,_DIFFIO_L8n,_(DQ1L){slash}(_)-PadL1)") (class "Default")
      (node (ref "U1") (pin "L1") (pinfunction "IO,_DIFFIO_L8n,_(DQ1L)/(_)_L1") (pintype "bidirectional"))
    )
    (net (code "168") (name "unconnected-(U1B-IO,_DIFFIO_L8p,_(DQS1L{slash}CQ1L#,DPCLK1){slash}(DQS1L{slash}CQ1L#,DPCLK1)-PadL2)") (class "Default")
      (node (ref "U1") (pin "L2") (pinfunction "IO,_DIFFIO_L8p,_(DQS1L/CQ1L#,DPCLK1)/(DQS1L/CQ1L#,DPCLK1)_L2") (pintype "bidirectional"))
    )
    (net (code "169") (name "unconnected-(U1B-IO,_DIFFIO_L9n,_(DQ1L){slash}(_)-PadN1)") (class "Default")
      (node (ref "U1") (pin "N1") (pinfunction "IO,_DIFFIO_L9n,_(DQ1L)/(_)_N1") (pintype "bidirectional"))
    )
    (net (code "170") (name "unconnected-(U1B-IO,_DIFFIO_L9p,_(DQ1L){slash}(_)-PadN2)") (class "Default")
      (node (ref "U1") (pin "N2") (pinfunction "IO,_DIFFIO_L9p,_(DQ1L)/(_)_N2") (pintype "bidirectional"))
    )
    (net (code "171") (name "unconnected-(U1B-IO,_DIFFIO_L10n,_(DM1L{slash}BWS#1L){slash}(_)-PadP1)") (class "Default")
      (node (ref "U1") (pin "P1") (pinfunction "IO,_DIFFIO_L10n,_(DM1L/BWS#1L)/(_)_P1") (pintype "bidirectional"))
    )
    (net (code "172") (name "unconnected-(U1B-IO,_DIFFIO_L10p,_(DQ1L){slash}(_)-PadP2)") (class "Default")
      (node (ref "U1") (pin "P2") (pinfunction "IO,_DIFFIO_L10p,_(DQ1L)/(_)_P2") (pintype "bidirectional"))
    )
    (net (code "173") (name "unconnected-(U1B-IO,_RDN1,_(DQ1L){slash}(_)-PadL4)") (class "Default")
      (node (ref "U1") (pin "L4") (pinfunction "IO,_RDN1,_(DQ1L)/(_)_L4") (pintype "bidirectional"))
    )
    (net (code "174") (name "unconnected-(U1B-IO,_RUP1,_(DQ1L){slash}(_)-PadK5)") (class "Default")
      (node (ref "U1") (pin "K5") (pinfunction "IO,_RUP1,_(DQ1L)/(_)_K5") (pintype "bidirectional"))
    )
    (net (code "175") (name "unconnected-(U1B-IO,_VREFB2N0-PadL3)") (class "Default")
      (node (ref "U1") (pin "L3") (pinfunction "IO,_VREFB2N0_L3") (pintype "bidirectional"))
    )
    (net (code "176") (name "unconnected-(U1B-IO-PadJ6)") (class "Default")
      (node (ref "U1") (pin "J6") (pinfunction "IO_J6") (pintype "bidirectional"))
    )
    (net (code "177") (name "unconnected-(U1C-IO,_(DQ3B){slash}(DQ5B)-PadL7)") (class "Default")
      (node (ref "U1") (pin "L7") (pinfunction "IO,_(DQ3B)/(DQ5B)_L7") (pintype "bidirectional"))
    )
    (net (code "178") (name "unconnected-(U1C-IO,_(DQ3B){slash}(DQ5B)-PadM6)") (class "Default")
      (node (ref "U1") (pin "M6") (pinfunction "IO,_(DQ3B)/(DQ5B)_M6") (pintype "bidirectional"))
    )
    (net (code "179") (name "unconnected-(U1C-IO,_(DQS1B{slash}CQ1B#,DPCLK2){slash}(DQS1B{slash}CQ1B#,DPCLK2)-PadT2)") (class "Default")
      (node (ref "U1") (pin "T2") (pinfunction "IO,_(DQS1B/CQ1B#,DPCLK2)/(DQS1B/CQ1B#,DPCLK2)_T2") (pintype "bidirectional"))
    )
    (net (code "180") (name "unconnected-(U1C-IO,_DIFFIO_B1n,_(DM3B{slash}BWS#3B){slash}(DM5B{slash}BWS#5B)-PadP3)") (class "Default")
      (node (ref "U1") (pin "P3") (pinfunction "IO,_DIFFIO_B1n,_(DM3B/BWS#3B)/(DM5B/BWS#5B)_P3") (pintype "bidirectional"))
    )
    (net (code "181") (name "unconnected-(U1C-IO,_DIFFIO_B1p-PadN3)") (class "Default")
      (node (ref "U1") (pin "N3") (pinfunction "IO,_DIFFIO_B1p_N3") (pintype "bidirectional"))
    )
    (net (code "182") (name "unconnected-(U1C-IO,_DIFFIO_B4n,_(DQ3B){slash}(DQ5B)-PadN6)") (class "Default")
      (node (ref "U1") (pin "N6") (pinfunction "IO,_DIFFIO_B4n,_(DQ3B)/(DQ5B)_N6") (pintype "bidirectional"))
    )
    (net (code "183") (name "unconnected-(U1C-IO,_DIFFIO_B4p,_(DQ3B){slash}(DQ5B)-PadN5)") (class "Default")
      (node (ref "U1") (pin "N5") (pinfunction "IO,_DIFFIO_B4p,_(DQ3B)/(DQ5B)_N5") (pintype "bidirectional"))
    )
    (net (code "184") (name "unconnected-(U1C-IO,_DIFFIO_B5n-PadK8)") (class "Default")
      (node (ref "U1") (pin "K8") (pinfunction "IO,_DIFFIO_B5n_K8") (pintype "bidirectional"))
    )
    (net (code "185") (name "unconnected-(U1C-IO,_DIFFIO_B5p,_(DQS3B{slash}CQ3B#){slash}(DQS3B{slash}CQ3B#)-PadM7)") (class "Default")
      (node (ref "U1") (pin "M7") (pinfunction "IO,_DIFFIO_B5p,_(DQS3B/CQ3B#)/(DQS3B/CQ3B#)_M7") (pintype "bidirectional"))
    )
    (net (code "186") (name "unconnected-(U1C-IO,_DIFFIO_B9n,_(DM5B{slash}BWS#5B){slash}(DM5B{slash}BWS#5B)-PadM8)") (class "Default")
      (node (ref "U1") (pin "M8") (pinfunction "IO,_DIFFIO_B9n,_(DM5B/BWS#5B)/(DM5B/BWS#5B)_M8") (pintype "bidirectional"))
    )
    (net (code "187") (name "unconnected-(U1C-IO,_DIFFIO_B9p,_(DQ3B){slash}(DQ5B)-PadL8)") (class "Default")
      (node (ref "U1") (pin "L8") (pinfunction "IO,_DIFFIO_B9p,_(DQ3B)/(DQ5B)_L8") (pintype "bidirectional"))
    )
    (net (code "188") (name "unconnected-(U1C-IO,_DIFFIO_B10n,_(DQ5B){slash}(DQ5B)-PadP8)") (class "Default")
      (node (ref "U1") (pin "P8") (pinfunction "IO,_DIFFIO_B10n,_(DQ5B)/(DQ5B)_P8") (pintype "bidirectional"))
    )
    (net (code "189") (name "unconnected-(U1C-IO,_DIFFIO_B10p,_(DQ5B){slash}(DQ5B)-PadN8)") (class "Default")
      (node (ref "U1") (pin "N8") (pinfunction "IO,_DIFFIO_B10p,_(DQ5B)/(DQ5B)_N8") (pintype "bidirectional"))
    )
    (net (code "190") (name "unconnected-(U1C-IO,_VREFB3N0-PadP6)") (class "Default")
      (node (ref "U1") (pin "P6") (pinfunction "IO,_VREFB3N0_P6") (pintype "bidirectional"))
    )
    (net (code "191") (name "unconnected-(U1D-IO,_(DQS2B{slash}CQ3B){slash}(DQS2B{slash}CQ3B)-PadP9)") (class "Default")
      (node (ref "U1") (pin "P9") (pinfunction "IO,_(DQS2B/CQ3B)/(DQS2B/CQ3B)_P9") (pintype "bidirectional"))
    )
    (net (code "192") (name "unconnected-(U1D-IO,_DIFFIO_B13n-PadL9)") (class "Default")
      (node (ref "U1") (pin "L9") (pinfunction "IO,_DIFFIO_B13n_L9") (pintype "bidirectional"))
    )
    (net (code "193") (name "unconnected-(U1D-IO,_DIFFIO_B13p-PadK9)") (class "Default")
      (node (ref "U1") (pin "K9") (pinfunction "IO,_DIFFIO_B13p_K9") (pintype "bidirectional"))
    )
    (net (code "194") (name "unconnected-(U1D-IO,_DIFFIO_B14n,_(DQ5B){slash}(DQ5B)-PadN9)") (class "Default")
      (node (ref "U1") (pin "N9") (pinfunction "IO,_DIFFIO_B14n,_(DQ5B)/(DQ5B)_N9") (pintype "bidirectional"))
    )
    (net (code "195") (name "unconnected-(U1D-IO,_DIFFIO_B14p-PadM9)") (class "Default")
      (node (ref "U1") (pin "M9") (pinfunction "IO,_DIFFIO_B14p_M9") (pintype "bidirectional"))
    )
    (net (code "196") (name "unconnected-(U1D-IO,_DIFFIO_B18n-PadL10)") (class "Default")
      (node (ref "U1") (pin "L10") (pinfunction "IO,_DIFFIO_B18n_L10") (pintype "bidirectional"))
    )
    (net (code "197") (name "unconnected-(U1D-IO,_DIFFIO_B18p-PadK10)") (class "Default")
      (node (ref "U1") (pin "K10") (pinfunction "IO,_DIFFIO_B18p_K10") (pintype "bidirectional"))
    )
    (net (code "198") (name "unconnected-(U1D-IO,_DIFFIO_B21n-PadL11)") (class "Default")
      (node (ref "U1") (pin "L11") (pinfunction "IO,_DIFFIO_B21n_L11") (pintype "bidirectional"))
    )
    (net (code "199") (name "unconnected-(U1D-IO,_DIFFIO_B22p-PadM11)") (class "Default")
      (node (ref "U1") (pin "M11") (pinfunction "IO,_DIFFIO_B22p_M11") (pintype "bidirectional"))
    )
    (net (code "200") (name "unconnected-(U1D-IO,_RUP2-PadM10)") (class "Default")
      (node (ref "U1") (pin "M10") (pinfunction "IO,_RUP2_M10") (pintype "bidirectional"))
    )
    (net (code "201") (name "unconnected-(U1D-IO,_VREFB4N0-PadP11)") (class "Default")
      (node (ref "U1") (pin "P11") (pinfunction "IO,_VREFB4N0_P11") (pintype "bidirectional"))
    )
    (net (code "202") (name "unconnected-(U1E-IO,_(DQ1R){slash}(_)-PadJ13)") (class "Default")
      (node (ref "U1") (pin "J13") (pinfunction "IO,_(DQ1R)/(_)_J13") (pintype "bidirectional"))
    )
    (net (code "203") (name "unconnected-(U1E-IO,_(DQ1R){slash}(_)-PadL13)") (class "Default")
      (node (ref "U1") (pin "L13") (pinfunction "IO,_(DQ1R)/(_)_L13") (pintype "bidirectional"))
    )
    (net (code "204") (name "unconnected-(U1E-IO,_DIFFIO_R6n,_(DQ1R){slash}(_)-PadJ14)") (class "Default")
      (node (ref "U1") (pin "J14") (pinfunction "IO,_DIFFIO_R6n,_(DQ1R)/(_)_J14") (pintype "bidirectional"))
    )
    (net (code "205") (name "unconnected-(U1E-IO,_DIFFIO_R6p-PadJ12)") (class "Default")
      (node (ref "U1") (pin "J12") (pinfunction "IO,_DIFFIO_R6p_J12") (pintype "bidirectional"))
    )
    (net (code "206") (name "unconnected-(U1E-IO,_DIFFIO_R11n,_(DQS3R{slash}CQ3R#){slash}(DQS3R{slash}CQ3R#)-PadP16)") (class "Default")
      (node (ref "U1") (pin "P16") (pinfunction "IO,_DIFFIO_R11n,_(DQS3R/CQ3R#)/(DQS3R/CQ3R#)_P16") (pintype "bidirectional"))
    )
    (net (code "207") (name "unconnected-(U1E-IO,_DIFFIO_R11p,_(DQ1R){slash}(_)-PadR16)") (class "Default")
      (node (ref "U1") (pin "R16") (pinfunction "IO,_DIFFIO_R11p,_(DQ1R)/(_)_R16") (pintype "bidirectional"))
    )
    (net (code "208") (name "unconnected-(U1E-IO,_RDN3,_(DQ1R){slash}(_)-PadP15)") (class "Default")
      (node (ref "U1") (pin "P15") (pinfunction "IO,_RDN3,_(DQ1R)/(_)_P15") (pintype "bidirectional"))
    )
    (net (code "209") (name "unconnected-(U1E-IO,_RUP3,_(DM1R{slash}BWS#1R){slash}(_)-PadN14)") (class "Default")
      (node (ref "U1") (pin "N14") (pinfunction "IO,_RUP3,_(DM1R/BWS#1R)/(_)_N14") (pintype "bidirectional"))
    )
    (net (code "210") (name "unconnected-(U1E-IO,_VREFB5N0-PadL14)") (class "Default")
      (node (ref "U1") (pin "L14") (pinfunction "IO,_VREFB5N0_L14") (pintype "bidirectional"))
    )
    (net (code "211") (name "unconnected-(U1E-IO-PadJ11)") (class "Default")
      (node (ref "U1") (pin "J11") (pinfunction "IO_J11") (pintype "bidirectional"))
    )
    (net (code "212") (name "unconnected-(U1E-IO-PadK11)") (class "Default")
      (node (ref "U1") (pin "K11") (pinfunction "IO_K11") (pintype "bidirectional"))
    )
    (net (code "213") (name "unconnected-(U1E-IO-PadK12)") (class "Default")
      (node (ref "U1") (pin "K12") (pinfunction "IO_K12") (pintype "bidirectional"))
    )
    (net (code "214") (name "unconnected-(U1E-IO-PadL12)") (class "Default")
      (node (ref "U1") (pin "L12") (pinfunction "IO_L12") (pintype "bidirectional"))
    )
    (net (code "215") (name "unconnected-(U1E-IO-PadM12)") (class "Default")
      (node (ref "U1") (pin "M12") (pinfunction "IO_M12") (pintype "bidirectional"))
    )
    (net (code "216") (name "unconnected-(U1E-IO-PadN13)") (class "Default")
      (node (ref "U1") (pin "N13") (pinfunction "IO_N13") (pintype "bidirectional"))
    )
    (net (code "217") (name "unconnected-(U1F-IO,_(DQS0R{slash}CQ1R,DPCLK5){slash}(DQS0R{slash}CQ1R,DPCLK5)-PadB16)") (class "Default")
      (node (ref "U1") (pin "B16") (pinfunction "IO,_(DQS0R/CQ1R,DPCLK5)/(DQS0R/CQ1R,DPCLK5)_B16") (pintype "bidirectional"))
    )
    (net (code "218") (name "unconnected-(U1F-IO,_DIFFIO_R1n,_(DQS2R{slash}CQ3R){slash}(DQS2R{slash}CQ3R)-PadC16)") (class "Default")
      (node (ref "U1") (pin "C16") (pinfunction "IO,_DIFFIO_R1n,_(DQS2R/CQ3R)/(DQS2R/CQ3R)_C16") (pintype "bidirectional"))
    )
    (net (code "219") (name "unconnected-(U1F-IO,_DIFFIO_R1p-PadC15)") (class "Default")
      (node (ref "U1") (pin "C15") (pinfunction "IO,_DIFFIO_R1p_C15") (pintype "bidirectional"))
    )
    (net (code "220") (name "unconnected-(U1F-IO,_DIFFIO_R2n-PadD16)") (class "Default")
      (node (ref "U1") (pin "D16") (pinfunction "IO,_DIFFIO_R2n_D16") (pintype "bidirectional"))
    )
    (net (code "221") (name "unconnected-(U1F-IO,_DIFFIO_R2p-PadD15)") (class "Default")
      (node (ref "U1") (pin "D15") (pinfunction "IO,_DIFFIO_R2p_D15") (pintype "bidirectional"))
    )
    (net (code "222") (name "unconnected-(U1F-IO,_DIFFIO_R3n,_(nCEO)-PadF16)") (class "Default")
      (node (ref "U1") (pin "F16") (pinfunction "IO,_DIFFIO_R3n,_(nCEO)_F16") (pintype "bidirectional"))
    )
    (net (code "223") (name "unconnected-(U1F-IO,_DIFFIO_R3p,_(CLKUSR)-PadF15)") (class "Default")
      (node (ref "U1") (pin "F15") (pinfunction "IO,_DIFFIO_R3p,_(CLKUSR)_F15") (pintype "bidirectional"))
    )
    (net (code "224") (name "unconnected-(U1F-IO,_DIFFIO_R4n,_(INIT_DONE)-PadG16)") (class "Default")
      (node (ref "U1") (pin "G16") (pinfunction "IO,_DIFFIO_R4n,_(INIT_DONE)_G16") (pintype "bidirectional"))
    )
    (net (code "225") (name "unconnected-(U1F-IO,_DIFFIO_R4p,_(CRC_ERROR)-PadG15)") (class "Default")
      (node (ref "U1") (pin "G15") (pinfunction "IO,_DIFFIO_R4p,_(CRC_ERROR)_G15") (pintype "bidirectional"))
    )
    (net (code "226") (name "unconnected-(U1F-IO,_VREFB6N0-PadF14)") (class "Default")
      (node (ref "U1") (pin "F14") (pinfunction "IO,_VREFB6N0_F14") (pintype "bidirectional"))
    )
    (net (code "227") (name "unconnected-(U1F-IO-PadF13)") (class "Default")
      (node (ref "U1") (pin "F13") (pinfunction "IO_F13") (pintype "bidirectional"))
    )
    (net (code "228") (name "unconnected-(U1F-IO-PadG11)") (class "Default")
      (node (ref "U1") (pin "G11") (pinfunction "IO_G11") (pintype "bidirectional"))
    )
    (net (code "229") (name "unconnected-(U1G-IO,_(DQS4T{slash}CQ5T){slash}(DQS4T{slash}CQ5T)-PadE9)") (class "Default")
      (node (ref "U1") (pin "E9") (pinfunction "IO,_(DQS4T/CQ5T)/(DQS4T/CQ5T)_E9") (pintype "bidirectional"))
    )
    (net (code "230") (name "unconnected-(U1G-IO,_DIFFIO_T13p,_(DM5T{slash}BWS#5T){slash}(DM5T{slash}BWS#5T)-PadD9)") (class "Default")
      (node (ref "U1") (pin "D9") (pinfunction "IO,_DIFFIO_T13p,_(DM5T/BWS#5T)/(DM5T/BWS#5T)_D9") (pintype "bidirectional"))
    )
    (net (code "231") (name "unconnected-(U1G-IO,_DIFFIO_T15n-PadF11)") (class "Default")
      (node (ref "U1") (pin "F11") (pinfunction "IO,_DIFFIO_T15n_F11") (pintype "bidirectional"))
    )
    (net (code "232") (name "unconnected-(U1G-IO,_DIFFIO_T20n-PadD11)") (class "Default")
      (node (ref "U1") (pin "D11") (pinfunction "IO,_DIFFIO_T20n_D11") (pintype "bidirectional"))
    )
    (net (code "233") (name "unconnected-(U1G-IO,_DIFFIO_T20p,_(DQS0T{slash}CQ1T,DPCLK6){slash}(DQS0T{slash}CQ1T,DPCLK6)-PadD12)") (class "Default")
      (node (ref "U1") (pin "D12") (pinfunction "IO,_DIFFIO_T20p,_(DQS0T/CQ1T,DPCLK6)/(DQS0T/CQ1T,DPCLK6)_D12") (pintype "bidirectional"))
    )
    (net (code "234") (name "unconnected-(U1G-IO,_DIFFIO_T21p,_(DQ5T){slash}(DQ5T)-PadD14)") (class "Default")
      (node (ref "U1") (pin "D14") (pinfunction "IO,_DIFFIO_T21p,_(DQ5T)/(DQ5T)_D14") (pintype "bidirectional"))
    )
    (net (code "235") (name "unconnected-(U1G-IO,_RDN4-PadE10)") (class "Default")
      (node (ref "U1") (pin "E10") (pinfunction "IO,_RDN4_E10") (pintype "bidirectional"))
    )
    (net (code "236") (name "unconnected-(U1G-IO,_RUP4-PadE11)") (class "Default")
      (node (ref "U1") (pin "E11") (pinfunction "IO,_RUP4_E11") (pintype "bidirectional"))
    )
    (net (code "237") (name "unconnected-(U1H-IO,_(DQ3T){slash}(DQ5T)-PadD8)") (class "Default")
      (node (ref "U1") (pin "D8") (pinfunction "IO,_(DQ3T)/(DQ5T)_D8") (pintype "bidirectional"))
    )
  )
)
